# Solenoid_Driver.net
KiCad netlist of a schematic drawn in Altium Designer
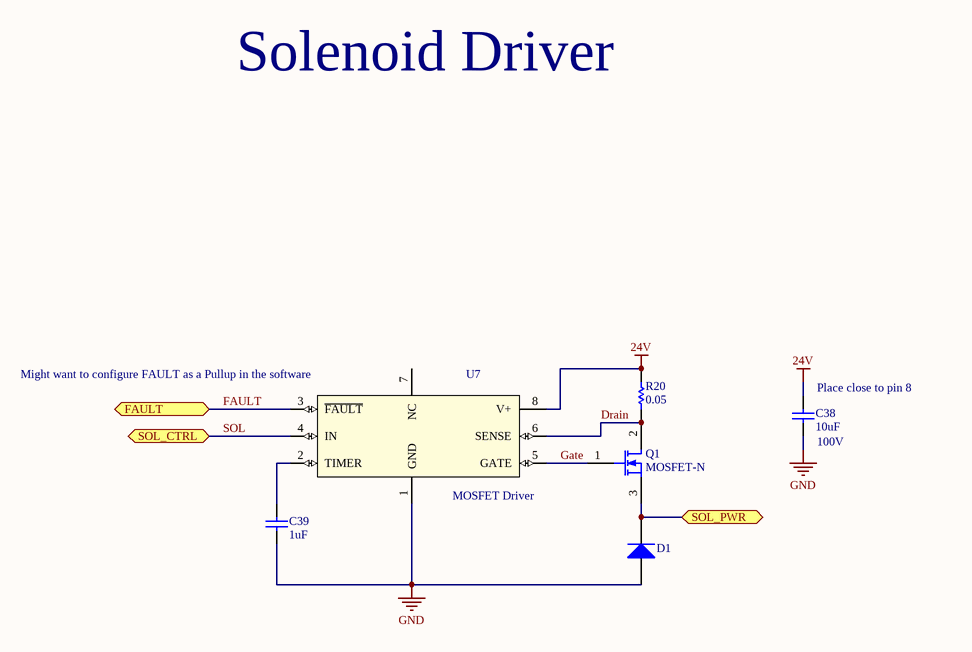
[diagram p0: Solenoid_Driver.SchDoc]

(export (version "E")
  (design (tool "Eeschema 10.0.6"))
  (components
    (comp (ref "C38")
      (value "10uF")
      (footprint "1206")
      (description "Capacitor")
      (fields (field (name "VOLTAGE") "100V") (field (name "Comment") "Cap"))
      (libsource (lib "Miscellaneous Devices") (part "Cap"))
    )
    (comp (ref "C39")
      (value "1uF")
      (footprint "0603")
      (description "Capacitor")
      (fields (field (name "Comment") "Cap"))
      (libsource (lib "Miscellaneous Devices") (part "Cap"))
    )
    (comp (ref "D1")
      (value "Diode")
      (footprint "SMC")
      (description "Default Diode")
      (libsource (lib "Miscellaneous Devices") (part "Diode"))
    )
    (comp (ref "Q1")
      (value "MOSFET-N")
      (footprint "DPAK2")
      (description "N-Channel MOSFET")
      (libsource (lib "Miscellaneous Devices") (part "MOSFET-N"))
    )
    (comp (ref "R20")
      (value "0.05")
      (footprint "0603")
      (description "Resistor")
      (fields (field (name "Comment") "Res1"))
      (libsource (lib "Miscellaneous Devices") (part "Res1"))
    )
    (comp (ref "U7")
      (value "MOSFET Driver")
      (footprint "PSO-8")
      (fields (field (name "MANUFACTURER_PART_NUMBER") "lt1910es8#pbf"))
      (libsource (lib "LaunchyRIOComponents") (part "LT1910ES8#PBF"))
    )
  )
  (nets
    (net (code "1") (name "/Drain") (class "Default")
      (node (ref "Q1") (pin "2") (pinfunction "D_2") (pintype "passive"))
      (node (ref "R20") (pin "1") (pinfunction "1_1") (pintype "passive"))
      (node (ref "U7") (pin "6") (pinfunction "SENSE_6") (pintype "bidirectional"))
    )
    (net (code "2") (name "/FAULT") (class "Default")
      (node (ref "U7") (pin "3") (pinfunction "~{FAULT}_3") (pintype "bidirectional"))
    )
    (net (code "3") (name "/Gate") (class "Default")
      (node (ref "Q1") (pin "1") (pinfunction "G_1") (pintype "passive"))
      (node (ref "U7") (pin "5") (pinfunction "GATE_5") (pintype "bidirectional"))
    )
    (net (code "4") (name "/SOL") (class "Default")
      (node (ref "U7") (pin "4") (pinfunction "IN_4") (pintype "bidirectional"))
    )
    (net (code "5") (name "/SOL_PWR") (class "Default")
      (node (ref "D1") (pin "2") (pinfunction "K_2") (pintype "passive"))
      (node (ref "Q1") (pin "3") (pinfunction "S_3") (pintype "passive"))
    )
    (net (code "6") (name "24V") (class "Default")
      (node (ref "C38") (pin "2") (pinfunction "2_2") (pintype "passive"))
      (node (ref "R20") (pin "2") (pinfunction "2_2") (pintype "passive"))
      (node (ref "U7") (pin "8") (pinfunction "V+_8") (pintype "power_in"))
    )
    (net (code "7") (name "GND") (class "Default")
      (node (ref "C38") (pin "1") (pinfunction "1_1") (pintype "passive"))
      (node (ref "C39") (pin "1") (pinfunction "1_1") (pintype "passive"))
      (node (ref "D1") (pin "1") (pinfunction "A_1") (pintype "passive"))
      (node (ref "U7") (pin "1") (pinfunction "GND_1") (pintype "power_in"))
    )
    (net (code "8") (name "Net-(U7-TIMER)") (class "Default")
      (node (ref "C39") (pin "2") (pinfunction "2_2") (pintype "passive"))
      (node (ref "U7") (pin "2") (pinfunction "TIMER_2") (pintype "bidirectional"))
    )
    (net (code "9") (name "unconnected-(U7-NC-Pad7)") (class "Default")
      (node (ref "U7") (pin "7") (pinfunction "NC_7") (pintype "passive"))
    )
  )
)
